# CTS_Teensy_Board_v1_1.net
KiCad netlist of a schematic drawn in EAGLE
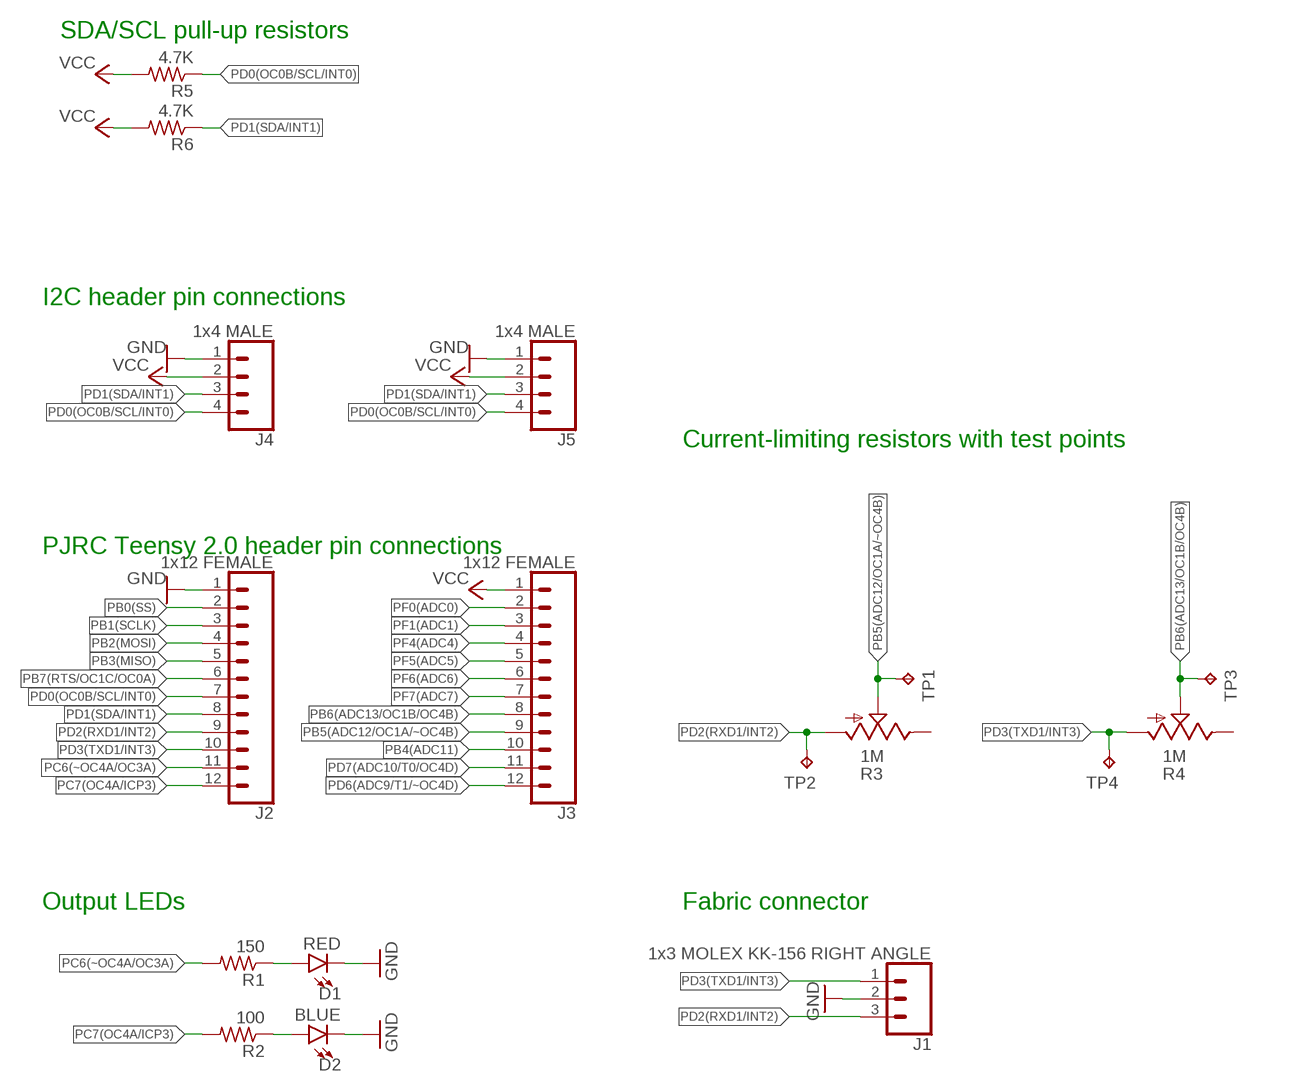
[diagram p0: schematic, sheet 1]

(export (version "E")
  (design (tool "Eeschema 10.0.6"))
  (components
    (comp (ref "D1")
      (value "RED")
      (footprint "eagle-import:LED_3MM")
      (libsource (lib "eagle-import") (part "LED3MM"))
    )
    (comp (ref "D2")
      (value "BLUE")
      (footprint "eagle-import:LED_3MM")
      (libsource (lib "eagle-import") (part "LED3MM"))
    )
    (comp (ref "J1")
      (value "1x3 MOLEX KK-156 RIGHT ANGLE")
      (footprint "eagle-import:MOLEX-1X3")
      (libsource (lib "eagle-import") (part "CONN_03POLAR"))
    )
    (comp (ref "J2")
      (value "1x12 FEMALE")
      (footprint "eagle-import:1X12")
      (libsource (lib "eagle-import") (part "CONN_12"))
    )
    (comp (ref "J3")
      (value "1x12 FEMALE")
      (footprint "eagle-import:1X12")
      (libsource (lib "eagle-import") (part "CONN_12"))
    )
    (comp (ref "J4")
      (value "1x4 MALE")
      (footprint "eagle-import:1X04")
      (libsource (lib "eagle-import") (part "CONN_04"))
    )
    (comp (ref "J5")
      (value "1x4 MALE")
      (footprint "eagle-import:1X04")
      (libsource (lib "eagle-import") (part "CONN_04"))
    )
    (comp (ref "R1")
      (value "150")
      (footprint "eagle-import:0204_7")
      (libsource (lib "eagle-import") (part "R-US_0204/7"))
    )
    (comp (ref "R2")
      (value "100")
      (footprint "eagle-import:0204_7")
      (libsource (lib "eagle-import") (part "R-US_0204/7"))
    )
    (comp (ref "R3")
      (value "1M")
      (footprint "eagle-import:SP19L")
      (libsource (lib "eagle-import") (part "TRIM_US-B90P"))
    )
    (comp (ref "R4")
      (value "1M")
      (footprint "eagle-import:SP19L")
      (libsource (lib "eagle-import") (part "TRIM_US-B90P"))
    )
    (comp (ref "R5")
      (value "4.7K")
      (footprint "eagle-import:0204_7")
      (libsource (lib "eagle-import") (part "R-US_0204/7"))
    )
    (comp (ref "R6")
      (value "4.7K")
      (footprint "eagle-import:0204_7")
      (libsource (lib "eagle-import") (part "R-US_0204/7"))
    )
    (comp (ref "TP1")
      (value "TPTP18R")
      (footprint "eagle-import:TP18R")
      (libsource (lib "eagle-import") (part "TPTP18R"))
    )
    (comp (ref "TP2")
      (value "TPTP18R")
      (footprint "eagle-import:TP18R")
      (libsource (lib "eagle-import") (part "TPTP18R"))
    )
    (comp (ref "TP3")
      (value "TPTP18R")
      (footprint "eagle-import:TP18R")
      (libsource (lib "eagle-import") (part "TPTP18R"))
    )
    (comp (ref "TP4")
      (value "TPTP18R")
      (footprint "eagle-import:TP18R")
      (libsource (lib "eagle-import") (part "TPTP18R"))
    )
  )
  (nets
    (net (code "1") (name "/PB5(ADC12{slash}OC1A{slash}~{OC4B})") (class "Default")
      (node (ref "J3") (pin "9") (pinfunction "9_9") (pintype "passive"))
      (node (ref "R3") (pin "S") (pinfunction "S_S") (pintype "passive"))
      (node (ref "TP1") (pin "TP") (pinfunction "TP_TP") (pintype "input"))
    )
    (net (code "2") (name "/PC6(~{OC4A{slash}OC3A})") (class "Default")
      (node (ref "J2") (pin "11") (pinfunction "11_11") (pintype "passive"))
      (node (ref "R1") (pin "2") (pinfunction "2_2") (pintype "passive"))
    )
    (net (code "3") (name "/PD6(ADC9{slash}T1{slash}~{OC4D})") (class "Default")
      (node (ref "J3") (pin "12") (pinfunction "12_12") (pintype "passive"))
    )
    (net (code "4") (name "GND") (class "Default")
      (node (ref "D1") (pin "K") (pinfunction "C_K") (pintype "passive"))
      (node (ref "D2") (pin "K") (pinfunction "C_K") (pintype "passive"))
      (node (ref "J1") (pin "2") (pinfunction "2_2") (pintype "passive"))
      (node (ref "J2") (pin "1") (pinfunction "1_1") (pintype "passive"))
      (node (ref "J4") (pin "1") (pinfunction "1_1") (pintype "passive"))
      (node (ref "J5") (pin "1") (pinfunction "1_1") (pintype "passive"))
    )
    (net (code "5") (name "Net-(D1-PadA)") (class "Default")
      (node (ref "D1") (pin "A") (pinfunction "A_A") (pintype "passive"))
      (node (ref "R1") (pin "1") (pinfunction "1_1") (pintype "passive"))
    )
    (net (code "6") (name "Net-(D2-PadA)") (class "Default")
      (node (ref "D2") (pin "A") (pinfunction "A_A") (pintype "passive"))
      (node (ref "R2") (pin "1") (pinfunction "1_1") (pintype "passive"))
    )
    (net (code "7") (name "PB0(SS)") (class "Default")
      (node (ref "J2") (pin "2") (pinfunction "2_2") (pintype "passive"))
    )
    (net (code "8") (name "PB1(SCLK)") (class "Default")
      (node (ref "J2") (pin "3") (pinfunction "3_3") (pintype "passive"))
    )
    (net (code "9") (name "PB2(MOSI)") (class "Default")
      (node (ref "J2") (pin "4") (pinfunction "4_4") (pintype "passive"))
    )
    (net (code "10") (name "PB3(MISO)") (class "Default")
      (node (ref "J2") (pin "5") (pinfunction "5_5") (pintype "passive"))
    )
    (net (code "11") (name "PB4(ADC11)") (class "Default")
      (node (ref "J3") (pin "10") (pinfunction "10_10") (pintype "passive"))
    )
    (net (code "12") (name "PB6(ADC13{slash}OC1B{slash}OC4B)") (class "Default")
      (node (ref "J3") (pin "8") (pinfunction "8_8") (pintype "passive"))
      (node (ref "R4") (pin "S") (pinfunction "S_S") (pintype "passive"))
      (node (ref "TP3") (pin "TP") (pinfunction "TP_TP") (pintype "input"))
    )
    (net (code "13") (name "PB7(RTS{slash}OC1C{slash}OC0A)") (class "Default")
      (node (ref "J2") (pin "6") (pinfunction "6_6") (pintype "passive"))
    )
    (net (code "14") (name "PC7(OC4A{slash}ICP3)") (class "Default")
      (node (ref "J2") (pin "12") (pinfunction "12_12") (pintype "passive"))
      (node (ref "R2") (pin "2") (pinfunction "2_2") (pintype "passive"))
    )
    (net (code "15") (name "PD0(OC0B{slash}SCL{slash}INT0)") (class "Default")
      (node (ref "J2") (pin "7") (pinfunction "7_7") (pintype "passive"))
      (node (ref "J4") (pin "4") (pinfunction "4_4") (pintype "passive"))
      (node (ref "J5") (pin "4") (pinfunction "4_4") (pintype "passive"))
      (node (ref "R5") (pin "1") (pinfunction "1_1") (pintype "passive"))
    )
    (net (code "16") (name "PD1(SDA{slash}INT1)") (class "Default")
      (node (ref "J2") (pin "8") (pinfunction "8_8") (pintype "passive"))
      (node (ref "J4") (pin "3") (pinfunction "3_3") (pintype "passive"))
      (node (ref "J5") (pin "3") (pinfunction "3_3") (pintype "passive"))
      (node (ref "R6") (pin "1") (pinfunction "1_1") (pintype "passive"))
    )
    (net (code "17") (name "PD2(RXD1{slash}INT2)") (class "Default")
      (node (ref "J1") (pin "3") (pinfunction "3_3") (pintype "passive"))
      (node (ref "J2") (pin "9") (pinfunction "9_9") (pintype "passive"))
      (node (ref "R3") (pin "A") (pinfunction "A_A") (pintype "passive"))
      (node (ref "TP2") (pin "TP") (pinfunction "TP_TP") (pintype "input"))
    )
    (net (code "18") (name "PD3(TXD1{slash}INT3)") (class "Default")
      (node (ref "J1") (pin "1") (pinfunction "1_1") (pintype "passive"))
      (node (ref "J2") (pin "10") (pinfunction "10_10") (pintype "passive"))
      (node (ref "R4") (pin "A") (pinfunction "A_A") (pintype "passive"))
      (node (ref "TP4") (pin "TP") (pinfunction "TP_TP") (pintype "input"))
    )
    (net (code "19") (name "PD7(ADC10{slash}T0{slash}OC4D)") (class "Default")
      (node (ref "J3") (pin "11") (pinfunction "11_11") (pintype "passive"))
    )
    (net (code "20") (name "PF0(ADC0)") (class "Default")
      (node (ref "J3") (pin "2") (pinfunction "2_2") (pintype "passive"))
    )
    (net (code "21") (name "PF1(ADC1)") (class "Default")
      (node (ref "J3") (pin "3") (pinfunction "3_3") (pintype "passive"))
    )
    (net (code "22") (name "PF4(ADC4)") (class "Default")
      (node (ref "J3") (pin "4") (pinfunction "4_4") (pintype "passive"))
    )
    (net (code "23") (name "PF5(ADC5)") (class "Default")
      (node (ref "J3") (pin "5") (pinfunction "5_5") (pintype "passive"))
    )
    (net (code "24") (name "PF6(ADC6)") (class "Default")
      (node (ref "J3") (pin "6") (pinfunction "6_6") (pintype "passive"))
    )
    (net (code "25") (name "PF7(ADC7)") (class "Default")
      (node (ref "J3") (pin "7") (pinfunction "7_7") (pintype "passive"))
    )
    (net (code "26") (name "VCC") (class "Default")
      (node (ref "J3") (pin "1") (pinfunction "1_1") (pintype "passive"))
      (node (ref "J4") (pin "2") (pinfunction "2_2") (pintype "passive"))
      (node (ref "J5") (pin "2") (pinfunction "2_2") (pintype "passive"))
      (node (ref "R5") (pin "2") (pinfunction "2_2") (pintype "passive"))
      (node (ref "R6") (pin "2") (pinfunction "2_2") (pintype "passive"))
    )
    (net (code "27") (name "unconnected-(R3-PadE)") (class "Default")
      (node (ref "R3") (pin "E") (pinfunction "E_E") (pintype "passive"))
    )
    (net (code "28") (name "unconnected-(R4-PadE)") (class "Default")
      (node (ref "R4") (pin "E") (pinfunction "E_E") (pintype "passive"))
    )
  )
)
